# 5APOWER.net
KiCad netlist of a schematic drawn in Altium Designer
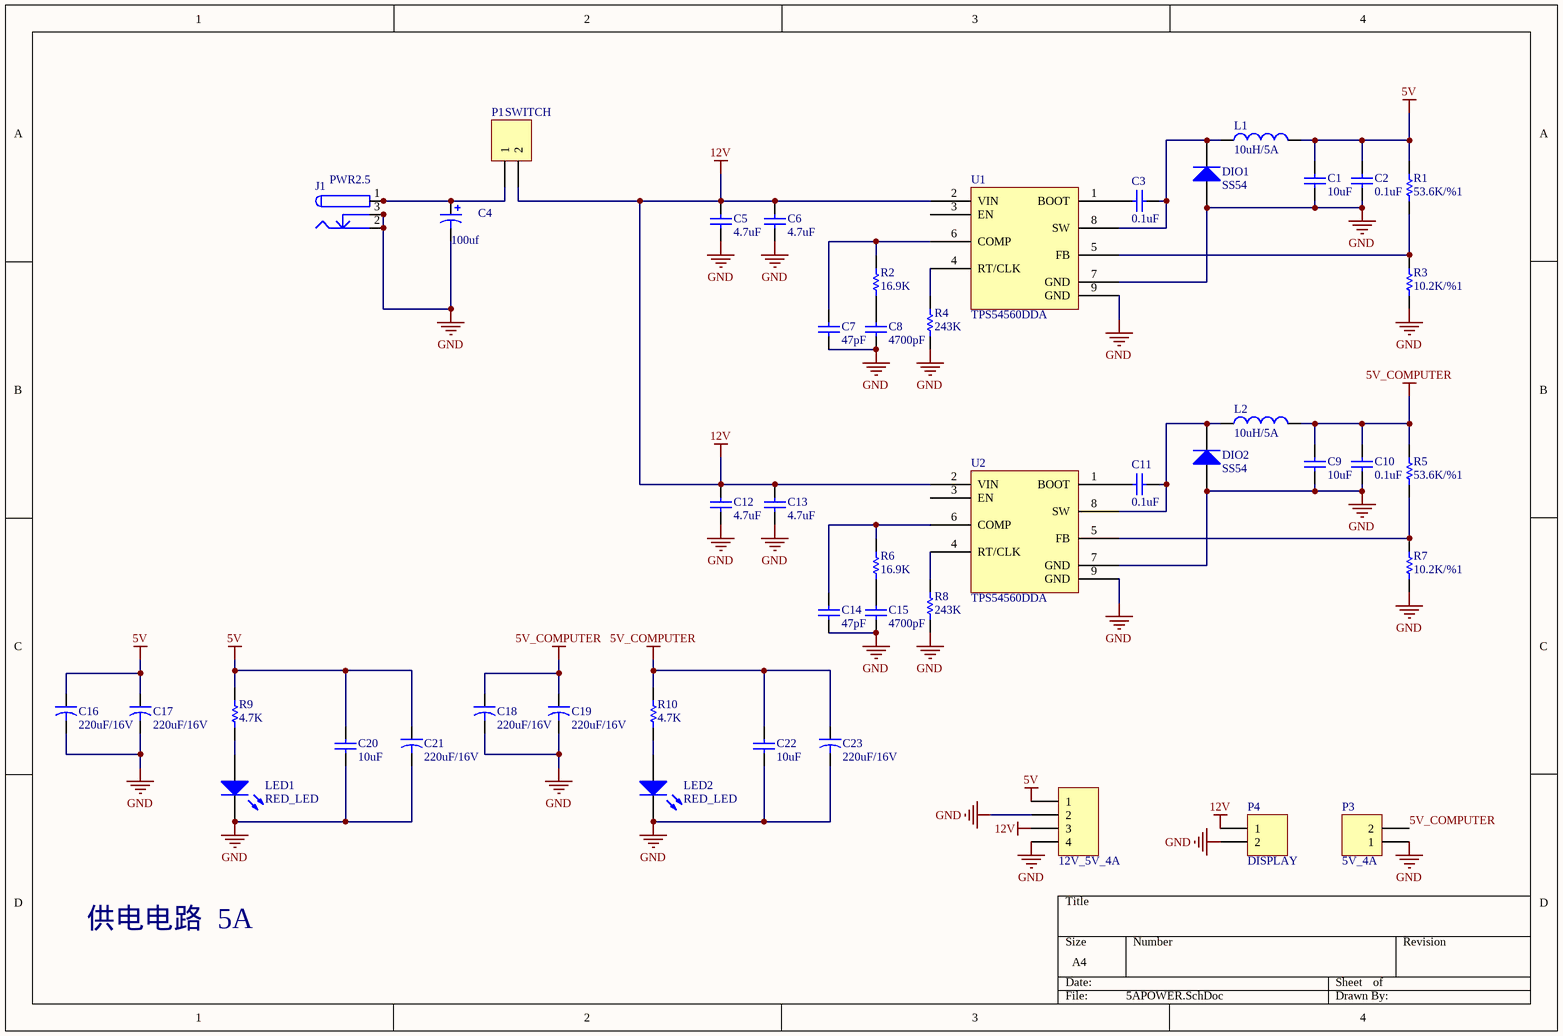
[diagram p0: 5APOWER.SchDoc]

(export (version "E")
  (design (tool "Eeschema 10.0.6"))
  (components
    (comp (ref "C1") (value "10uF") (footprint "0805C") (libsource (lib "XS") (part "CAP")))
    (comp (ref "C2") (value "0.1uF") (footprint "0805C") (libsource (lib "XS") (part "CAP")))
    (comp (ref "C3") (value "0.1uF") (footprint "0805C") (libsource (lib "XS") (part "CAP")))
    (comp (ref "C4")
      (value "100uf")
      (footprint "S-C6.6-H7.2")
      (description "Polarized Capacitor (Radial)")
      (fields (field (name "PUBLISHER") "Altium Limited"))
      (libsource (lib "Miscellaneous Devices") (part "Cap Pol1"))
    )
    (comp (ref "C5") (value "4.7uF") (footprint "0805C") (libsource (lib "XS") (part "CAP")))
    (comp (ref "C6") (value "4.7uF") (footprint "0805C") (libsource (lib "XS") (part "CAP")))
    (comp (ref "C7") (value "47pF") (footprint "0805C") (libsource (lib "XS") (part "CAP")))
    (comp (ref "C8") (value "4700pF") (footprint "0805C") (libsource (lib "XS") (part "CAP")))
    (comp (ref "C9") (value "10uF") (footprint "0805C") (libsource (lib "XS") (part "CAP")))
    (comp (ref "C10") (value "0.1uF") (footprint "0805C") (libsource (lib "XS") (part "CAP")))
    (comp (ref "C11") (value "0.1uF") (footprint "0805C") (libsource (lib "XS") (part "CAP")))
    (comp (ref "C12") (value "4.7uF") (footprint "0805C") (libsource (lib "XS") (part "CAP")))
    (comp (ref "C13") (value "4.7uF") (footprint "0805C") (libsource (lib "XS") (part "CAP")))
    (comp (ref "C14") (value "47pF") (footprint "0805C") (libsource (lib "XS") (part "CAP")))
    (comp (ref "C15") (value "4700pF") (footprint "0805C") (libsource (lib "XS") (part "CAP")))
    (comp (ref "C16")
      (value "220uF/16V")
      (footprint "S-C6.6-H7.2")
      (description "铝电解电容")
      (libsource (lib "XS") (part "CAP-SOP"))
    )
    (comp (ref "C17")
      (value "220uF/16V")
      (footprint "S-C6.6-H7.2")
      (description "铝电解电容")
      (libsource (lib "XS") (part "CAP-SOP"))
    )
    (comp (ref "C18")
      (value "220uF/16V")
      (footprint "S-C6.6-H7.2")
      (description "铝电解电容")
      (libsource (lib "XS") (part "CAP-SOP"))
    )
    (comp (ref "C19")
      (value "220uF/16V")
      (footprint "S-C6.6-H7.2")
      (description "铝电解电容")
      (libsource (lib "XS") (part "CAP-SOP"))
    )
    (comp (ref "C20") (value "10uF") (footprint "0805C") (libsource (lib "XS") (part "CAP")))
    (comp (ref "C21")
      (value "220uF/16V")
      (footprint "S-C6.6-H7.2")
      (description "铝电解电容")
      (libsource (lib "XS") (part "CAP-SOP"))
    )
    (comp (ref "C22") (value "10uF") (footprint "0805C") (libsource (lib "XS") (part "CAP")))
    (comp (ref "C23")
      (value "220uF/16V")
      (footprint "S-C6.6-H7.2")
      (description "铝电解电容")
      (libsource (lib "XS") (part "CAP-SOP"))
    )
    (comp (ref "DIO1") (value "SS54") (footprint "SMB-B") (libsource (lib "XS") (part "IN5822")))
    (comp (ref "DIO2") (value "SS54") (footprint "SMB-B") (libsource (lib "XS") (part "IN5822")))
    (comp (ref "J1")
      (value "PWR2.5")
      (footprint "DC10B")
      (description "Low Voltage Power Supply Connector")
      (fields (field (name "PUBLISHER") "Altium Limited"))
      (libsource (lib "Miscellaneous Connectors") (part "PWR2.5"))
    )
    (comp (ref "L1") (value "10uH/5A") (footprint "L-7X7S") (libsource (lib "XS") (part "L")))
    (comp (ref "L2") (value "10uH/5A") (footprint "L-7X7S") (libsource (lib "XS") (part "L")))
    (comp (ref "LED1") (value "RED_LED") (footprint "0805D") (libsource (lib "XS") (part "LED")))
    (comp (ref "LED2") (value "RED_LED") (footprint "0805D") (libsource (lib "XS") (part "LED")))
    (comp (ref "P1")
      (value "SWITCH")
      (footprint "2.54-2P")
      (description "Header, 2-Pin")
      (fields (field (name "PUBLISHER") "Altium Limited"))
      (libsource (lib "") (part "Header 2_2"))
    )
    (comp (ref "P2")
      (value "12V_5V_4A")
      (footprint "2.54-4p")
      (description "Header, 4-Pin")
      (fields (field (name "PUBLISHER") "Altium Limited"))
      (libsource (lib "Miscellaneous Connectors") (part "Header 4"))
    )
    (comp (ref "P3")
      (value "5V_4A")
      (footprint "2.54-2P")
      (description "Header, 2-Pin")
      (fields (field (name "PUBLISHER") "Altium Limited"))
      (libsource (lib "Miscellaneous Connectors") (part "Header 2"))
    )
    (comp (ref "P4")
      (value "DISPLAY")
      (footprint "2.54-2P")
      (description "Header, 2-Pin")
      (fields (field (name "PUBLISHER") "Altium Limited"))
      (libsource (lib "") (part "Header 2_1"))
    )
    (comp (ref "R1")
      (value "53.6K/%1")
      (footprint "0805_RES")
      (description "精密电阻")
      (libsource (lib "XS") (part "RES"))
    )
    (comp (ref "R2") (value "16.9K") (footprint "0805_RES") (libsource (lib "XS") (part "RES")))
    (comp (ref "R3")
      (value "10.2K/%1")
      (footprint "0805_RES")
      (description "精密电阻")
      (libsource (lib "XS") (part "RES"))
    )
    (comp (ref "R4") (value "243K") (footprint "0805_RES") (libsource (lib "XS") (part "RES")))
    (comp (ref "R5")
      (value "53.6K/%1")
      (footprint "0805_RES")
      (description "精密电阻")
      (libsource (lib "XS") (part "RES"))
    )
    (comp (ref "R6") (value "16.9K") (footprint "0805_RES") (libsource (lib "XS") (part "RES")))
    (comp (ref "R7")
      (value "10.2K/%1")
      (footprint "0805_RES")
      (description "精密电阻")
      (libsource (lib "XS") (part "RES"))
    )
    (comp (ref "R8") (value "243K") (footprint "0805_RES") (libsource (lib "XS") (part "RES")))
    (comp (ref "R9") (value "4.7K") (footprint "0805_RES") (libsource (lib "XS") (part "RES")))
    (comp (ref "R10") (value "4.7K") (footprint "0805_RES") (libsource (lib "XS") (part "RES")))
    (comp (ref "U1")
      (value "TPS54560DDA")
      (footprint "SO08")
      (description "电源芯片")
      (libsource (lib "XS") (part "TPS54560DDA"))
    )
    (comp (ref "U2")
      (value "TPS54560DDA")
      (footprint "SO08")
      (description "电源芯片")
      (libsource (lib "XS") (part "TPS54560DDA"))
    )
  )
  (nets
    (net (code "1") (name "5V") (class "Default")
      (node (ref "C1") (pin "2") (pinfunction "2_2") (pintype "passive"))
      (node (ref "C16") (pin "A") (pinfunction "A_A") (pintype "passive"))
      (node (ref "C17") (pin "A") (pinfunction "A_A") (pintype "passive"))
      (node (ref "C2") (pin "2") (pinfunction "2_2") (pintype "passive"))
      (node (ref "C20") (pin "2") (pinfunction "2_2") (pintype "passive"))
      (node (ref "C21") (pin "A") (pinfunction "A_A") (pintype "passive"))
      (node (ref "L1") (pin "2") (pinfunction "2_2") (pintype "passive"))
      (node (ref "P2") (pin "1") (pinfunction "1_1") (pintype "passive"))
      (node (ref "R1") (pin "1") (pinfunction "1_1") (pintype "passive"))
      (node (ref "R9") (pin "1") (pinfunction "1_1") (pintype "passive"))
    )
    (net (code "2") (name "5V_COMPUTER") (class "Default")
      (node (ref "C10") (pin "2") (pinfunction "2_2") (pintype "passive"))
      (node (ref "C18") (pin "A") (pinfunction "A_A") (pintype "passive"))
      (node (ref "C19") (pin "A") (pinfunction "A_A") (pintype "passive"))
      (node (ref "C22") (pin "2") (pinfunction "2_2") (pintype "passive"))
      (node (ref "C23") (pin "A") (pinfunction "A_A") (pintype "passive"))
      (node (ref "C9") (pin "2") (pinfunction "2_2") (pintype "passive"))
      (node (ref "L2") (pin "2") (pinfunction "2_2") (pintype "passive"))
      (node (ref "P3") (pin "2") (pinfunction "2_2") (pintype "passive"))
      (node (ref "R10") (pin "1") (pinfunction "1_1") (pintype "passive"))
      (node (ref "R5") (pin "1") (pinfunction "1_1") (pintype "passive"))
    )
    (net (code "3") (name "12V") (class "Default")
      (node (ref "C12") (pin "2") (pinfunction "2_2") (pintype "passive"))
      (node (ref "C13") (pin "2") (pinfunction "2_2") (pintype "passive"))
      (node (ref "C5") (pin "2") (pinfunction "2_2") (pintype "passive"))
      (node (ref "C6") (pin "2") (pinfunction "2_2") (pintype "passive"))
      (node (ref "P1") (pin "2") (pinfunction "2_2") (pintype "passive"))
      (node (ref "P2") (pin "3") (pinfunction "3_3") (pintype "passive"))
      (node (ref "P4") (pin "1") (pinfunction "1_1") (pintype "passive"))
      (node (ref "U1") (pin "2") (pinfunction "VIN_2") (pintype "passive"))
      (node (ref "U2") (pin "2") (pinfunction "VIN_2") (pintype "passive"))
    )
    (net (code "4") (name "GND") (class "Default")
      (node (ref "C1") (pin "1") (pinfunction "1_1") (pintype "passive"))
      (node (ref "C10") (pin "1") (pinfunction "1_1") (pintype "passive"))
      (node (ref "C12") (pin "1") (pinfunction "1_1") (pintype "passive"))
      (node (ref "C13") (pin "1") (pinfunction "1_1") (pintype "passive"))
      (node (ref "C14") (pin "1") (pinfunction "1_1") (pintype "passive"))
      (node (ref "C15") (pin "1") (pinfunction "1_1") (pintype "passive"))
      (node (ref "C16") (pin "K") (pinfunction "K_K") (pintype "passive"))
      (node (ref "C17") (pin "K") (pinfunction "K_K") (pintype "passive"))
      (node (ref "C18") (pin "K") (pinfunction "K_K") (pintype "passive"))
      (node (ref "C19") (pin "K") (pinfunction "K_K") (pintype "passive"))
      (node (ref "C2") (pin "1") (pinfunction "1_1") (pintype "passive"))
      (node (ref "C20") (pin "1") (pinfunction "1_1") (pintype "passive"))
      (node (ref "C21") (pin "K") (pinfunction "K_K") (pintype "passive"))
      (node (ref "C22") (pin "1") (pinfunction "1_1") (pintype "passive"))
      (node (ref "C23") (pin "K") (pinfunction "K_K") (pintype "passive"))
      (node (ref "C4") (pin "K") (pinfunction "K_K") (pintype "passive"))
      (node (ref "C5") (pin "1") (pinfunction "1_1") (pintype "passive"))
      (node (ref "C6") (pin "1") (pinfunction "1_1") (pintype "passive"))
      (node (ref "C7") (pin "1") (pinfunction "1_1") (pintype "passive"))
      (node (ref "C8") (pin "1") (pinfunction "1_1") (pintype "passive"))
      (node (ref "C9") (pin "1") (pinfunction "1_1") (pintype "passive"))
      (node (ref "DIO1") (pin "A") (pinfunction "A_A") (pintype "passive"))
      (node (ref "DIO2") (pin "A") (pinfunction "A_A") (pintype "passive"))
      (node (ref "J1") (pin "2") (pinfunction "2_2") (pintype "power_in"))
      (node (ref "J1") (pin "2A") (pinfunction "2A_2A") (pintype "power_in"))
      (node (ref "J1") (pin "2B") (pinfunction "2B_2B") (pintype "power_in"))
      (node (ref "J1") (pin "3") (pinfunction "3_3") (pintype "power_in"))
      (node (ref "J1") (pin "3A") (pinfunction "3A_3A") (pintype "power_in"))
      (node (ref "J1") (pin "3B") (pinfunction "3B_3B") (pintype "power_in"))
      (node (ref "LED1") (pin "K") (pinfunction "K_K") (pintype "passive"))
      (node (ref "LED2") (pin "K") (pinfunction "K_K") (pintype "passive"))
      (node (ref "P2") (pin "2") (pinfunction "2_2") (pintype "passive"))
      (node (ref "P2") (pin "4") (pinfunction "4_4") (pintype "passive"))
      (node (ref "P3") (pin "1") (pinfunction "1_1") (pintype "passive"))
      (node (ref "P4") (pin "2") (pinfunction "2_2") (pintype "passive"))
      (node (ref "R3") (pin "2") (pinfunction "2_2") (pintype "passive"))
      (node (ref "R4") (pin "2") (pinfunction "2_2") (pintype "passive"))
      (node (ref "R7") (pin "2") (pinfunction "2_2") (pintype "passive"))
      (node (ref "R8") (pin "2") (pinfunction "2_2") (pintype "passive"))
      (node (ref "U1") (pin "7") (pinfunction "GND_7") (pintype "passive"))
      (node (ref "U1") (pin "9") (pinfunction "GND_9") (pintype "passive"))
      (node (ref "U2") (pin "7") (pinfunction "GND_7") (pintype "passive"))
      (node (ref "U2") (pin "9") (pinfunction "GND_9") (pintype "passive"))
    )
    (net (code "5") (name "Net-(C4-PadA)") (class "Default")
      (node (ref "C4") (pin "A") (pinfunction "A_A") (pintype "passive"))
      (node (ref "J1") (pin "1") (pinfunction "1_1") (pintype "power_in"))
      (node (ref "J1") (pin "1A") (pinfunction "1A_1A") (pintype "power_in"))
      (node (ref "J1") (pin "1B") (pinfunction "1B_1B") (pintype "power_in"))
      (node (ref "P1") (pin "1") (pinfunction "1_1") (pintype "passive"))
    )
    (net (code "6") (name "Net-(C8-Pad2)") (class "Default")
      (node (ref "C8") (pin "2") (pinfunction "2_2") (pintype "passive"))
      (node (ref "R2") (pin "2") (pinfunction "2_2") (pintype "passive"))
    )
    (net (code "7") (name "Net-(C15-Pad2)") (class "Default")
      (node (ref "C15") (pin "2") (pinfunction "2_2") (pintype "passive"))
      (node (ref "R6") (pin "2") (pinfunction "2_2") (pintype "passive"))
    )
    (net (code "8") (name "Net-(LED1-PadA)") (class "Default")
      (node (ref "LED1") (pin "A") (pinfunction "A_A") (pintype "passive"))
      (node (ref "R9") (pin "2") (pinfunction "2_2") (pintype "passive"))
    )
    (net (code "9") (name "Net-(LED2-PadA)") (class "Default")
      (node (ref "LED2") (pin "A") (pinfunction "A_A") (pintype "passive"))
      (node (ref "R10") (pin "2") (pinfunction "2_2") (pintype "passive"))
    )
    (net (code "10") (name "Net-(U1-BOOT)") (class "Default")
      (node (ref "C3") (pin "2") (pinfunction "2_2") (pintype "passive"))
      (node (ref "U1") (pin "1") (pinfunction "BOOT_1") (pintype "passive"))
    )
    (net (code "11") (name "Net-(U1-COMP)") (class "Default")
      (node (ref "C7") (pin "2") (pinfunction "2_2") (pintype "passive"))
      (node (ref "R2") (pin "1") (pinfunction "1_1") (pintype "passive"))
      (node (ref "U1") (pin "6") (pinfunction "COMP_6") (pintype "passive"))
    )
    (net (code "12") (name "Net-(U1-FB)") (class "Default")
      (node (ref "R1") (pin "2") (pinfunction "2_2") (pintype "passive"))
      (node (ref "R3") (pin "1") (pinfunction "1_1") (pintype "passive"))
      (node (ref "U1") (pin "5") (pinfunction "FB_5") (pintype "passive"))
    )
    (net (code "13") (name "Net-(U1-RT{slash}CLK)") (class "Default")
      (node (ref "R4") (pin "1") (pinfunction "1_1") (pintype "passive"))
      (node (ref "U1") (pin "4") (pinfunction "RT/CLK_4") (pintype "passive"))
    )
    (net (code "14") (name "Net-(U1-SW)") (class "Default")
      (node (ref "C3") (pin "1") (pinfunction "1_1") (pintype "passive"))
      (node (ref "DIO1") (pin "K") (pinfunction "K_K") (pintype "passive"))
      (node (ref "L1") (pin "1") (pinfunction "1_1") (pintype "passive"))
      (node (ref "U1") (pin "8") (pinfunction "SW_8") (pintype "passive"))
    )
    (net (code "15") (name "Net-(U2-BOOT)") (class "Default")
      (node (ref "C11") (pin "2") (pinfunction "2_2") (pintype "passive"))
      (node (ref "U2") (pin "1") (pinfunction "BOOT_1") (pintype "passive"))
    )
    (net (code "16") (name "Net-(U2-COMP)") (class "Default")
      (node (ref "C14") (pin "2") (pinfunction "2_2") (pintype "passive"))
      (node (ref "R6") (pin "1") (pinfunction "1_1") (pintype "passive"))
      (node (ref "U2") (pin "6") (pinfunction "COMP_6") (pintype "passive"))
    )
    (net (code "17") (name "Net-(U2-FB)") (class "Default")
      (node (ref "R5") (pin "2") (pinfunction "2_2") (pintype "passive"))
      (node (ref "R7") (pin "1") (pinfunction "1_1") (pintype "passive"))
      (node (ref "U2") (pin "5") (pinfunction "FB_5") (pintype "passive"))
    )
    (net (code "18") (name "Net-(U2-RT{slash}CLK)") (class "Default")
      (node (ref "R8") (pin "1") (pinfunction "1_1") (pintype "passive"))
      (node (ref "U2") (pin "4") (pinfunction "RT/CLK_4") (pintype "passive"))
    )
    (net (code "19") (name "Net-(U2-SW)") (class "Default")
      (node (ref "C11") (pin "1") (pinfunction "1_1") (pintype "passive"))
      (node (ref "DIO2") (pin "K") (pinfunction "K_K") (pintype "passive"))
      (node (ref "L2") (pin "1") (pinfunction "1_1") (pintype "passive"))
      (node (ref "U2") (pin "8") (pinfunction "SW_8") (pintype "passive"))
    )
    (net (code "20") (name "unconnected-(U1-EN-Pad3)") (class "Default")
      (node (ref "U1") (pin "3") (pinfunction "EN_3") (pintype "passive"))
    )
    (net (code "21") (name "unconnected-(U2-EN-Pad3)") (class "Default")
      (node (ref "U2") (pin "3") (pinfunction "EN_3") (pintype "passive"))
    )
  )
)
